# 8ALPSMultiplexerBoard.net
KiCad netlist of a schematic drawn in EAGLE
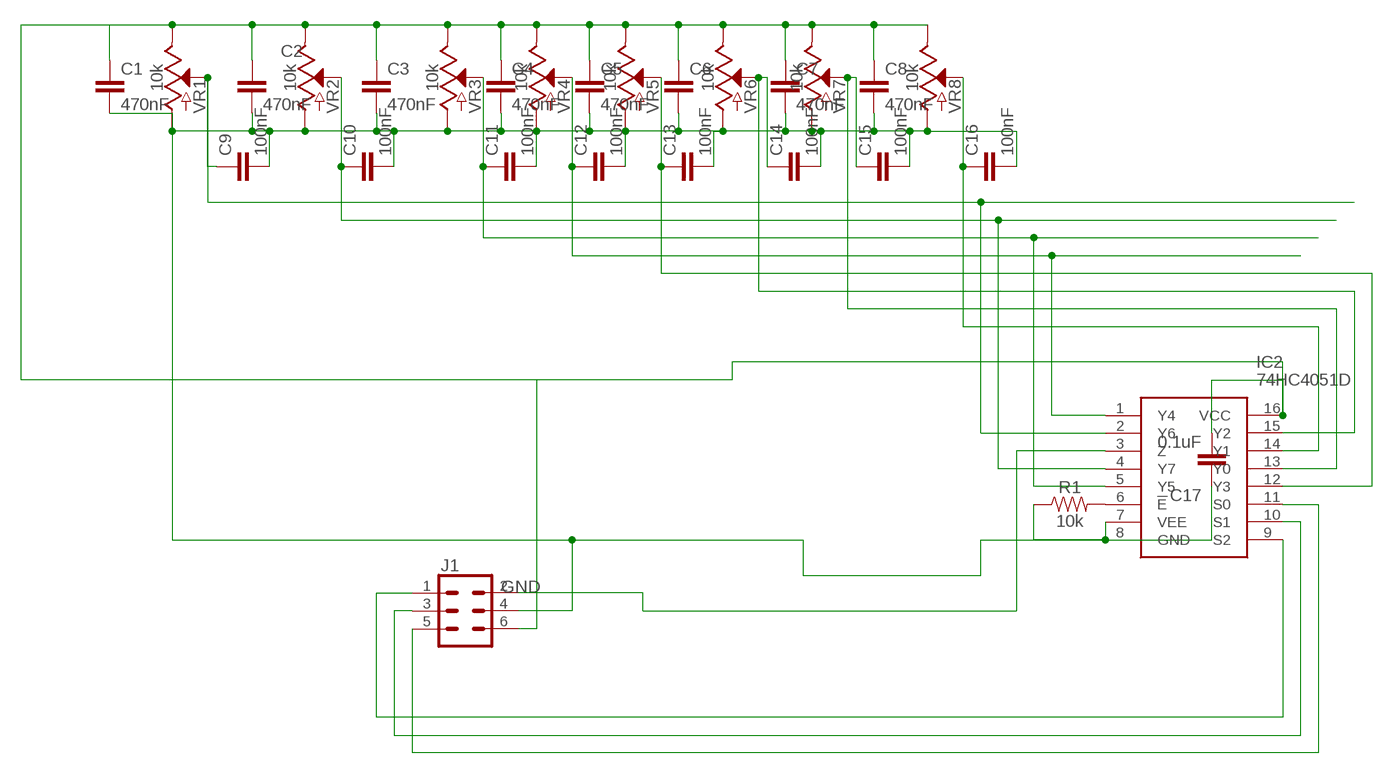
[diagram p0: schematic, sheet 1]

(export (version "E")
  (design (tool "Eeschema 10.0.6"))
  (components
    (comp (ref "C1")
      (value "470nF")
      (footprint "eagle-import:C0805")
      (libsource (lib "eagle-import") (part "C-EUC0805"))
    )
    (comp (ref "C2")
      (value "470nF")
      (footprint "eagle-import:C0805")
      (libsource (lib "eagle-import") (part "C-EUC0805"))
    )
    (comp (ref "C3")
      (value "470nF")
      (footprint "eagle-import:C0805")
      (libsource (lib "eagle-import") (part "C-EUC0805"))
    )
    (comp (ref "C4")
      (value "470nF")
      (footprint "eagle-import:C0805")
      (libsource (lib "eagle-import") (part "C-EUC0805"))
    )
    (comp (ref "C5")
      (value "470nF")
      (footprint "eagle-import:C0805")
      (libsource (lib "eagle-import") (part "C-EUC0805"))
    )
    (comp (ref "C6")
      (value "C-EUC0805")
      (footprint "eagle-import:C0805")
      (libsource (lib "eagle-import") (part "C-EUC0805"))
    )
    (comp (ref "C7")
      (value "470nF")
      (footprint "eagle-import:C0805")
      (libsource (lib "eagle-import") (part "C-EUC0805"))
    )
    (comp (ref "C8")
      (value "470nF")
      (footprint "eagle-import:C0805")
      (libsource (lib "eagle-import") (part "C-EUC0805"))
    )
    (comp (ref "C9")
      (value "100nF")
      (footprint "eagle-import:C0805")
      (libsource (lib "eagle-import") (part "C-EUC0805"))
    )
    (comp (ref "C10")
      (value "100nF")
      (footprint "eagle-import:C0805")
      (libsource (lib "eagle-import") (part "C-EUC0805"))
    )
    (comp (ref "C11")
      (value "100nF")
      (footprint "eagle-import:C0805")
      (libsource (lib "eagle-import") (part "C-EUC0805"))
    )
    (comp (ref "C12")
      (value "100nF")
      (footprint "eagle-import:C0805")
      (libsource (lib "eagle-import") (part "C-EUC0805"))
    )
    (comp (ref "C13")
      (value "100nF")
      (footprint "eagle-import:C0805")
      (libsource (lib "eagle-import") (part "C-EUC0805"))
    )
    (comp (ref "C14")
      (value "100nF")
      (footprint "eagle-import:C0805")
      (libsource (lib "eagle-import") (part "C-EUC0805"))
    )
    (comp (ref "C15")
      (value "100nF")
      (footprint "eagle-import:C0805")
      (libsource (lib "eagle-import") (part "C-EUC0805"))
    )
    (comp (ref "C16")
      (value "100nF")
      (footprint "eagle-import:C0805")
      (libsource (lib "eagle-import") (part "C-EUC0805"))
    )
    (comp (ref "C17")
      (value "0.1uF")
      (footprint "eagle-import:C0805")
      (libsource (lib "eagle-import") (part "C-EUC0805"))
    )
    (comp (ref "IC2")
      (value "74HC4051D")
      (footprint "eagle-import:SOIC127P600X175-16N")
      (libsource (lib "eagle-import") (part "74HC4051D"))
    )
    (comp (ref "J1")
      (value "CONN_03X2FEMALE")
      (footprint "eagle-import:2X3")
      (libsource (lib "eagle-import") (part "CONN_03X2FEMALE"))
    )
    (comp (ref "R1")
      (value "10k")
      (footprint "eagle-import:0805")
      (libsource (lib "eagle-import") (part "0.75OHM-0805-1/4W-1%"))
    )
    (comp (ref "VR1")
      (value "10k")
      (footprint "eagle-import:POT-PTH-ALPS")
      (libsource (lib "eagle-import") (part "POTENTIOMETER-PTH-9MM-1/20W-20%"))
    )
    (comp (ref "VR2")
      (value "10k")
      (footprint "eagle-import:POT-PTH-ALPS")
      (libsource (lib "eagle-import") (part "POTENTIOMETER-PTH-9MM-1/20W-20%"))
    )
    (comp (ref "VR3")
      (value "10k")
      (footprint "eagle-import:POT-PTH-ALPS")
      (libsource (lib "eagle-import") (part "POTENTIOMETER-PTH-9MM-1/20W-20%"))
    )
    (comp (ref "VR4")
      (value "10k")
      (footprint "eagle-import:POT-PTH-ALPS")
      (libsource (lib "eagle-import") (part "POTENTIOMETER-PTH-9MM-1/20W-20%"))
    )
    (comp (ref "VR5")
      (value "10k")
      (footprint "eagle-import:POT-PTH-ALPS")
      (libsource (lib "eagle-import") (part "POTENTIOMETER-PTH-9MM-1/20W-20%"))
    )
    (comp (ref "VR6")
      (value "10k")
      (footprint "eagle-import:POT-PTH-ALPS")
      (libsource (lib "eagle-import") (part "POTENTIOMETER-PTH-9MM-1/20W-20%"))
    )
    (comp (ref "VR7")
      (value "10k")
      (footprint "eagle-import:POT-PTH-ALPS")
      (libsource (lib "eagle-import") (part "POTENTIOMETER-PTH-9MM-1/20W-20%"))
    )
    (comp (ref "VR8")
      (value "10k")
      (footprint "eagle-import:POT-PTH-ALPS")
      (libsource (lib "eagle-import") (part "POTENTIOMETER-PTH-9MM-1/20W-20%"))
    )
  )
  (nets
    (net (code "1") (name "/GND") (class "Default")
      (node (ref "C1") (pin "2") (pinfunction "2_2") (pintype "passive"))
      (node (ref "C10") (pin "2") (pinfunction "2_2") (pintype "passive"))
      (node (ref "C11") (pin "2") (pinfunction "2_2") (pintype "passive"))
      (node (ref "C12") (pin "2") (pinfunction "2_2") (pintype "passive"))
      (node (ref "C13") (pin "2") (pinfunction "2_2") (pintype "passive"))
      (node (ref "C14") (pin "2") (pinfunction "2_2") (pintype "passive"))
      (node (ref "C15") (pin "2") (pinfunction "2_2") (pintype "passive"))
      (node (ref "C16") (pin "2") (pinfunction "2_2") (pintype "passive"))
      (node (ref "C17") (pin "1") (pinfunction "1_1") (pintype "passive"))
      (node (ref "C2") (pin "2") (pinfunction "2_2") (pintype "passive"))
      (node (ref "C3") (pin "2") (pinfunction "2_2") (pintype "passive"))
      (node (ref "C4") (pin "2") (pinfunction "2_2") (pintype "passive"))
      (node (ref "C5") (pin "2") (pinfunction "2_2") (pintype "passive"))
      (node (ref "C6") (pin "2") (pinfunction "2_2") (pintype "passive"))
      (node (ref "C7") (pin "2") (pinfunction "2_2") (pintype "passive"))
      (node (ref "C8") (pin "2") (pinfunction "2_2") (pintype "passive"))
      (node (ref "C9") (pin "2") (pinfunction "2_2") (pintype "passive"))
      (node (ref "IC2") (pin "7") (pinfunction "VEE_7") (pintype "bidirectional"))
      (node (ref "IC2") (pin "8") (pinfunction "GND_8") (pintype "bidirectional"))
      (node (ref "J1") (pin "4") (pinfunction "4_4") (pintype "bidirectional"))
      (node (ref "R1") (pin "1") (pinfunction "1_1") (pintype "passive"))
      (node (ref "VR1") (pin "P$3") (pinfunction "A_P$3") (pintype "passive"))
      (node (ref "VR2") (pin "P$3") (pinfunction "A_P$3") (pintype "passive"))
      (node (ref "VR3") (pin "P$3") (pinfunction "A_P$3") (pintype "passive"))
      (node (ref "VR4") (pin "P$3") (pinfunction "A_P$3") (pintype "passive"))
      (node (ref "VR5") (pin "P$3") (pinfunction "A_P$3") (pintype "passive"))
      (node (ref "VR6") (pin "P$3") (pinfunction "A_P$3") (pintype "passive"))
      (node (ref "VR7") (pin "P$3") (pinfunction "A_P$3") (pintype "passive"))
      (node (ref "VR8") (pin "P$3") (pinfunction "A_P$3") (pintype "passive"))
    )
    (net (code "2") (name "Net-(IC2-S0)") (class "Default")
      (node (ref "IC2") (pin "11") (pinfunction "S0_11") (pintype "bidirectional"))
      (node (ref "J1") (pin "5") (pinfunction "5_5") (pintype "bidirectional"))
    )
    (net (code "3") (name "Net-(IC2-S1)") (class "Default")
      (node (ref "IC2") (pin "10") (pinfunction "S1_10") (pintype "bidirectional"))
      (node (ref "J1") (pin "3") (pinfunction "3_3") (pintype "bidirectional"))
    )
    (net (code "4") (name "Net-(IC2-S2)") (class "Default")
      (node (ref "IC2") (pin "9") (pinfunction "S2_9") (pintype "bidirectional"))
      (node (ref "J1") (pin "1") (pinfunction "1_1") (pintype "bidirectional"))
    )
    (net (code "5") (name "Net-(IC2-VCC)") (class "Default")
      (node (ref "C1") (pin "1") (pinfunction "1_1") (pintype "passive"))
      (node (ref "C17") (pin "2") (pinfunction "2_2") (pintype "passive"))
      (node (ref "C2") (pin "1") (pinfunction "1_1") (pintype "passive"))
      (node (ref "C3") (pin "1") (pinfunction "1_1") (pintype "passive"))
      (node (ref "C4") (pin "1") (pinfunction "1_1") (pintype "passive"))
      (node (ref "C5") (pin "1") (pinfunction "1_1") (pintype "passive"))
      (node (ref "C6") (pin "1") (pinfunction "1_1") (pintype "passive"))
      (node (ref "C7") (pin "1") (pinfunction "1_1") (pintype "passive"))
      (node (ref "C8") (pin "1") (pinfunction "1_1") (pintype "passive"))
      (node (ref "IC2") (pin "16") (pinfunction "VCC_16") (pintype "bidirectional"))
      (node (ref "J1") (pin "6") (pinfunction "6_6") (pintype "bidirectional"))
      (node (ref "VR1") (pin "P$1") (pinfunction "E_P$1") (pintype "passive"))
      (node (ref "VR2") (pin "P$1") (pinfunction "E_P$1") (pintype "passive"))
      (node (ref "VR3") (pin "P$1") (pinfunction "E_P$1") (pintype "passive"))
      (node (ref "VR4") (pin "P$1") (pinfunction "E_P$1") (pintype "passive"))
      (node (ref "VR5") (pin "P$1") (pinfunction "E_P$1") (pintype "passive"))
      (node (ref "VR6") (pin "P$1") (pinfunction "E_P$1") (pintype "passive"))
      (node (ref "VR7") (pin "P$1") (pinfunction "E_P$1") (pintype "passive"))
      (node (ref "VR8") (pin "P$1") (pinfunction "E_P$1") (pintype "passive"))
    )
    (net (code "6") (name "Net-(IC2-Y0)") (class "Default")
      (node (ref "C15") (pin "1") (pinfunction "1_1") (pintype "passive"))
      (node (ref "IC2") (pin "13") (pinfunction "Y0_13") (pintype "bidirectional"))
      (node (ref "VR7") (pin "P$2") (pinfunction "S_P$2") (pintype "passive"))
    )
    (net (code "7") (name "Net-(IC2-Y1)") (class "Default")
      (node (ref "C16") (pin "1") (pinfunction "1_1") (pintype "passive"))
      (node (ref "IC2") (pin "14") (pinfunction "Y1_14") (pintype "bidirectional"))
      (node (ref "VR8") (pin "P$2") (pinfunction "S_P$2") (pintype "passive"))
    )
    (net (code "8") (name "Net-(IC2-Y2)") (class "Default")
      (node (ref "C14") (pin "1") (pinfunction "1_1") (pintype "passive"))
      (node (ref "IC2") (pin "15") (pinfunction "Y2_15") (pintype "bidirectional"))
      (node (ref "VR6") (pin "P$2") (pinfunction "S_P$2") (pintype "passive"))
    )
    (net (code "9") (name "Net-(IC2-Y3)") (class "Default")
      (node (ref "C13") (pin "1") (pinfunction "1_1") (pintype "passive"))
      (node (ref "IC2") (pin "12") (pinfunction "Y3_12") (pintype "bidirectional"))
      (node (ref "VR5") (pin "P$2") (pinfunction "S_P$2") (pintype "passive"))
    )
    (net (code "10") (name "Net-(IC2-Y4)") (class "Default")
      (node (ref "C12") (pin "1") (pinfunction "1_1") (pintype "passive"))
      (node (ref "IC2") (pin "1") (pinfunction "Y4_1") (pintype "bidirectional"))
      (node (ref "VR4") (pin "P$2") (pinfunction "S_P$2") (pintype "passive"))
    )
    (net (code "11") (name "Net-(IC2-Y5)") (class "Default")
      (node (ref "C11") (pin "1") (pinfunction "1_1") (pintype "passive"))
      (node (ref "IC2") (pin "5") (pinfunction "Y5_5") (pintype "bidirectional"))
      (node (ref "VR3") (pin "P$2") (pinfunction "S_P$2") (pintype "passive"))
    )
    (net (code "12") (name "Net-(IC2-Y6)") (class "Default")
      (node (ref "C9") (pin "1") (pinfunction "1_1") (pintype "passive"))
      (node (ref "IC2") (pin "2") (pinfunction "Y6_2") (pintype "bidirectional"))
      (node (ref "VR1") (pin "P$2") (pinfunction "S_P$2") (pintype "passive"))
    )
    (net (code "13") (name "Net-(IC2-Y7)") (class "Default")
      (node (ref "C10") (pin "1") (pinfunction "1_1") (pintype "passive"))
      (node (ref "IC2") (pin "4") (pinfunction "Y7_4") (pintype "bidirectional"))
      (node (ref "VR2") (pin "P$2") (pinfunction "S_P$2") (pintype "passive"))
    )
    (net (code "14") (name "Net-(IC2-Z)") (class "Default")
      (node (ref "IC2") (pin "3") (pinfunction "Z_3") (pintype "bidirectional"))
      (node (ref "J1") (pin "2") (pinfunction "2_2") (pintype "bidirectional"))
    )
    (net (code "15") (name "Net-(IC2-~{E})") (class "Default")
      (node (ref "IC2") (pin "6") (pinfunction "~{E}_6") (pintype "bidirectional"))
      (node (ref "R1") (pin "2") (pinfunction "2_2") (pintype "passive"))
    )
  )
)
